# Main_Sheet.net
KiCad netlist of a schematic drawn in Altium Designer
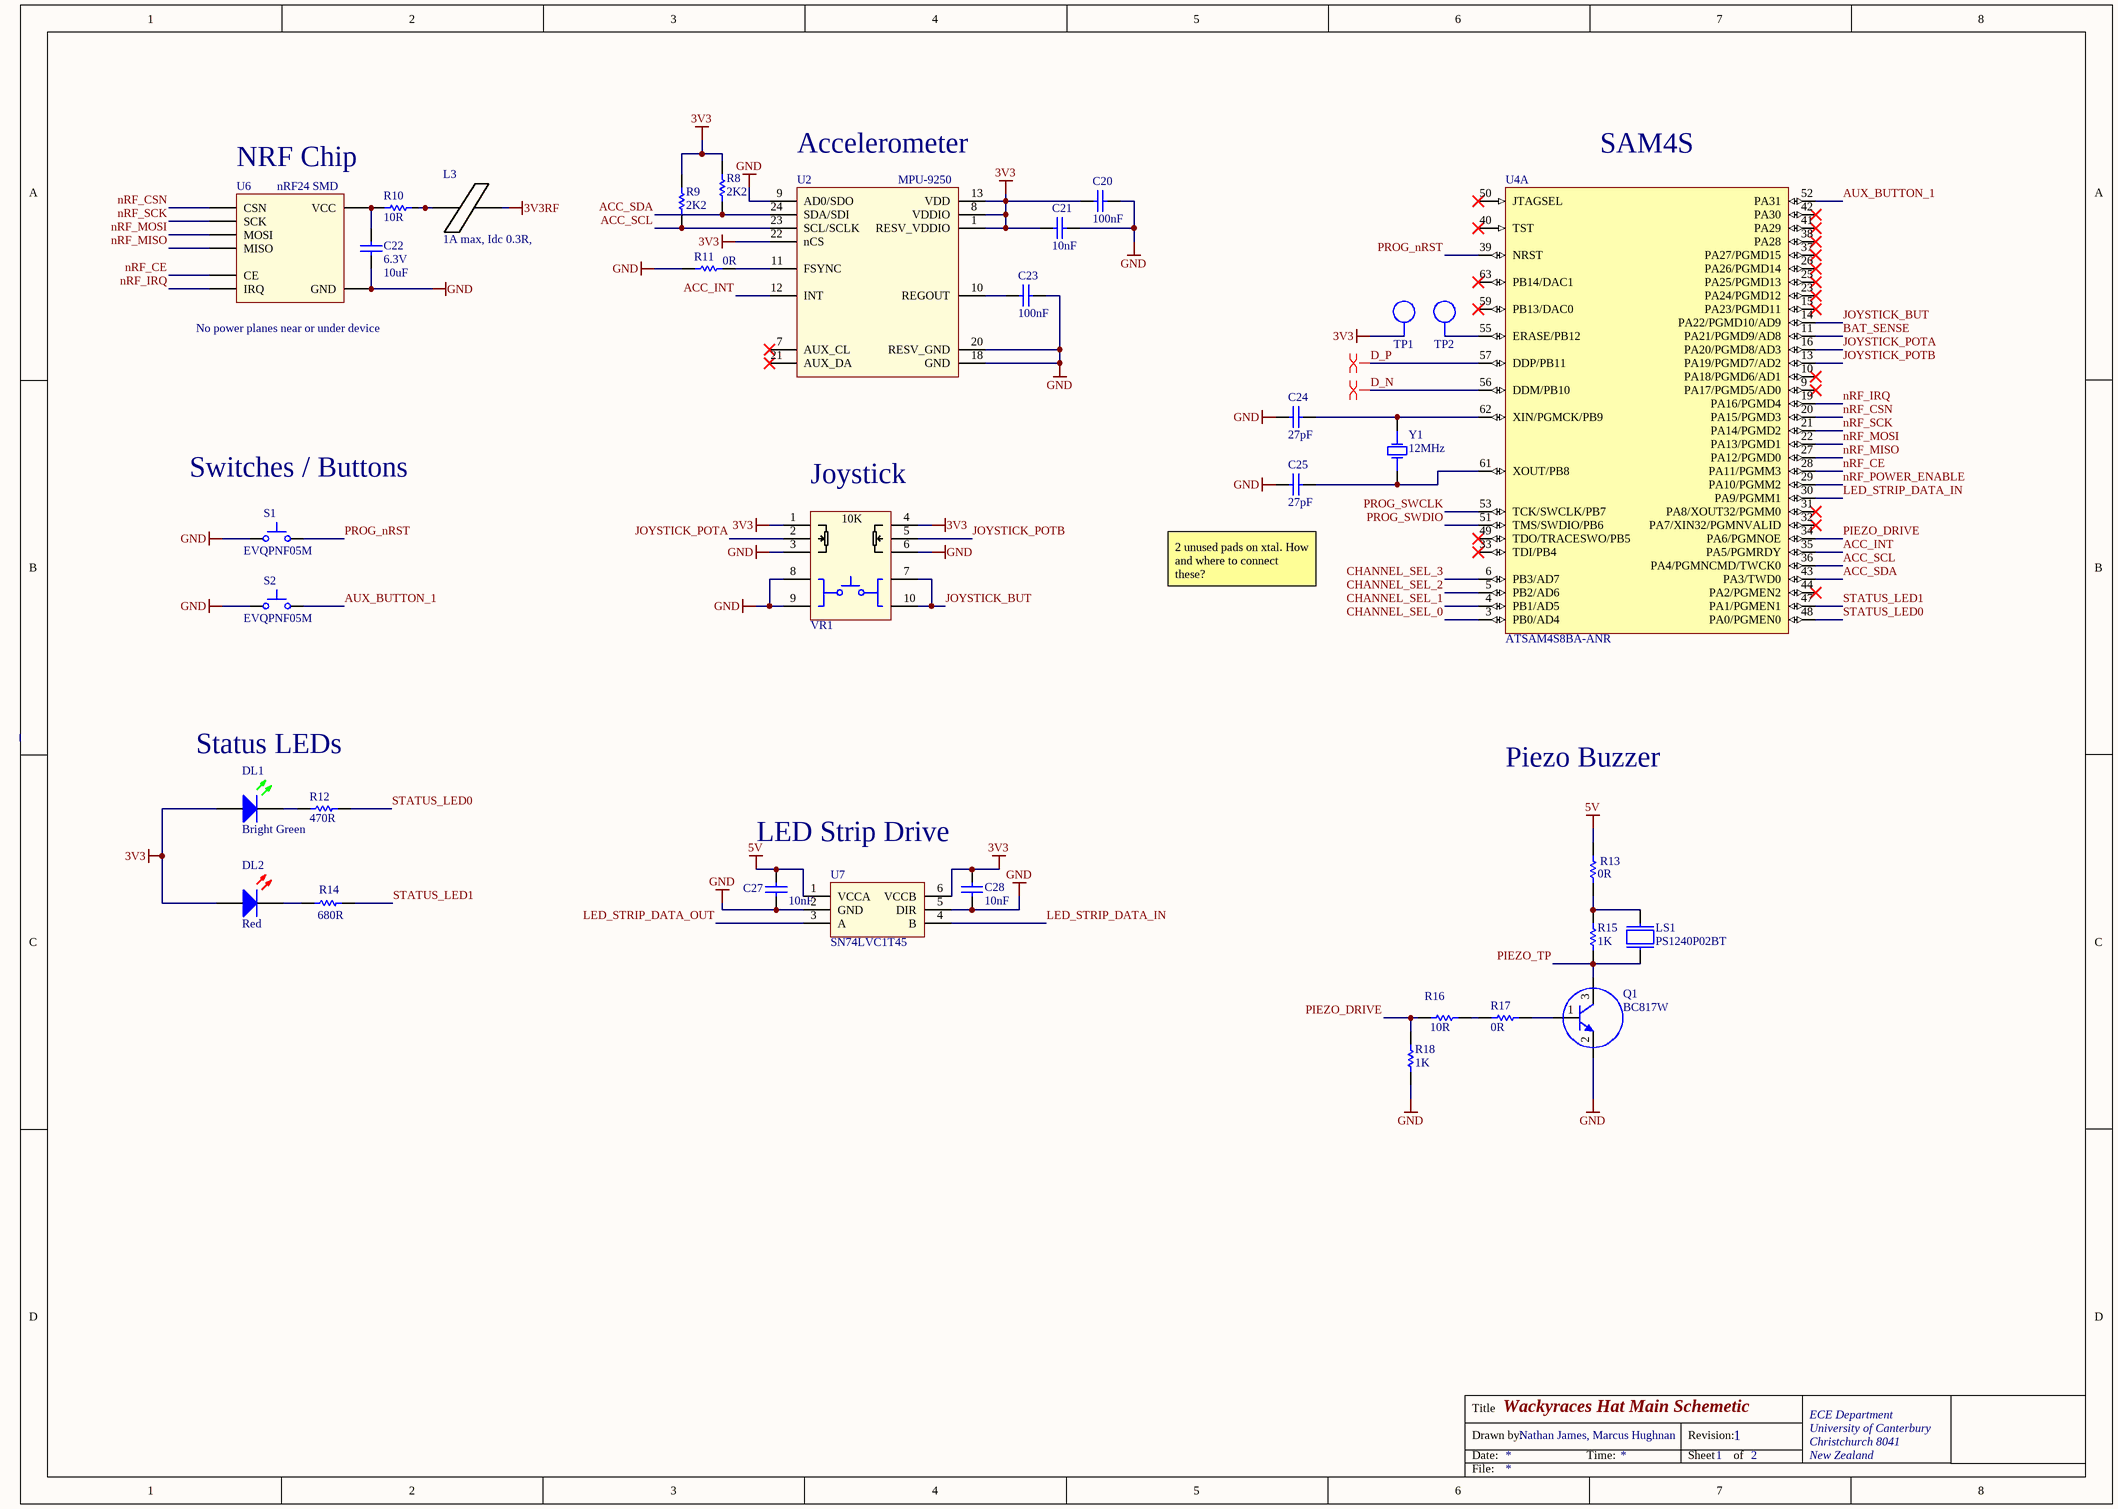
[diagram p0: Main Sheet.SchDoc]

(export (version "E")
  (design (tool "Eeschema 10.0.6"))
  (components
    (comp (ref "C20")
      (value "100nF")
      (footprint "CAPC1608L")
      (description "CAP CER 100nF X7R +-10% 50V 0603")
      (libsource (lib "ECE AD19Components_19V1") (part "CC_100nF_0603"))
    )
    (comp (ref "C21")
      (value "10nF")
      (footprint "CAPC1608L")
      (description "CAP CER 10nF X7R +-10% 50V 0603")
      (libsource (lib "ECE AD19Components_19V1") (part "CC_10nF_0603"))
    )
    (comp (ref "C22")
      (value "10uF")
      (footprint "CAPC1608L")
      (description "CAP CER 10UF X5R +-20% 6V3 0603")
      (fields (field (name "VOLTAGE - RATED") "6.3V"))
      (libsource (lib "ECE AD19Components_19V1") (part "CC_10uF_0603"))
    )
    (comp (ref "C23")
      (value "100nF")
      (footprint "CAPC1608L")
      (description "CAP CER 100nF X7R +-10% 50V 0603")
      (libsource (lib "ECE AD19Components_19V1") (part "CC_100nF_0603"))
    )
    (comp (ref "C24")
      (value "27pF")
      (footprint "CAPC1608L")
      (description "CAP CER 27pF NPO/COG +-5% 50V 0603")
      (libsource (lib "ECE AD19Components_19V1") (part "CC_27pF_0603"))
    )
    (comp (ref "C25")
      (value "27pF")
      (footprint "CAPC1608L")
      (description "CAP CER 27pF NPO/COG +-5% 50V 0603")
      (libsource (lib "ECE AD19Components_19V1") (part "CC_27pF_0603"))
    )
    (comp (ref "C27")
      (value "10nF")
      (footprint "CAPC1608L")
      (description "CAP CER 10nF X7R +-10% 50V 0603")
      (libsource (lib "ECE AD19Components_19V1") (part "CC_10nF_0603"))
    )
    (comp (ref "C28")
      (value "10nF")
      (footprint "CAPC1608L")
      (description "CAP CER 10nF X7R +-10% 50V 0603")
      (libsource (lib "ECE AD19Components_19V1") (part "CC_10nF_0603"))
    )
    (comp (ref "DL1")
      (value "Bright Green")
      (footprint "WL-SMCW0603")
      (description "LED Bright Green 40mcd 0603 SMD")
      (fields
        (field (name "MANUFACTURER") "WURTH ELEKTRONIK")
        (field (name "MANUFACTURER PART NUMBER") "150060VS75000")
        (field (name "LED COLOUR") "Bright Green")
      )
      (libsource (lib "ECE AD19Components_19V1") (part "DL_150060VS75000"))
    )
    (comp (ref "DL2")
      (value "Red")
      (footprint "WL-SMCW0603")
      (description "LED Red 250mcd 0603 SMD")
      (fields
        (field (name "MANUFACTURER") "WURTH ELEKTRONIK")
        (field (name "MANUFACTURER PART NUMBER") "150060RS75000")
        (field (name "LED COLOUR") "Red")
      )
      (libsource (lib "ECE AD19Components_19V1") (part "DL_150060RS75000"))
    )
    (comp (ref "L3")
      (value "1A max, Idc 0.3R,")
      (footprint "INDC3216L")
      (description "Ferrite Bead, Rdc 0.3R, Z100MHZ 600R, Imax 1A, SMD 1206")
      (fields
        (field (name "MANUFACTURER") "FAIR-RITE")
        (field (name "MANUFACTURER PART NUMBER") "2512066017Y1")
      )
      (libsource (lib "ECE AD19Components_19V1") (part "IN_Ferrite-Bead"))
    )
    (comp (ref "LS1")
      (value "PS1240P02BT")
      (footprint "XDCR_PS1240P02BT")
      (description "Buzzers Transducer, Externally Driven Piezo 3V 4kHz 60dB @ 3V, 10cm Through Hole PC Pins")
      (fields (field (name "MF") "TDK"))
      (libsource (lib "PS1240P02BT") (part "PS1240P02BT"))
    )
    (comp (ref "Q1")
      (value "BC817W")
      (footprint "SOT323_M")
      (description "NPN GP Bipolar Transistor 45V 500mA SOT323")
      (fields (field (name "MANUFACTURER") "NXP"))
      (libsource (lib "ECE AD19Components_19V1") (part "TB_BC817W"))
    )
    (comp (ref "R8")
      (value "2K2")
      (footprint "RESC1608L")
      (description "RES 2.2K OHM 1/10W 5% 0603 SMD")
      (libsource (lib "ECE AD19Components_19V1") (part "RS_2K2"))
    )
    (comp (ref "R9")
      (value "2K2")
      (footprint "RESC1608L")
      (description "RES 2.2K OHM 1/10W 5% 0603 SMD")
      (libsource (lib "ECE AD19Components_19V1") (part "RS_2K2"))
    )
    (comp (ref "R10")
      (value "10R")
      (footprint "RESC1608L")
      (description "RES 10 OHM 1/10W 5% 0603 SMD")
      (libsource (lib "ECE AD19Components_19V1") (part "RS_10R"))
    )
    (comp (ref "R11")
      (value "0R")
      (footprint "RESC1608L")
      (description "RES 0.0 OHM 1/10W 5% 0603 SMD")
      (libsource (lib "ECE AD19Components_19V1") (part "RS_0R0"))
    )
    (comp (ref "R12")
      (value "470R")
      (footprint "RESC1608L")
      (description "RES 470 OHM 1/10W 5% 0603 SMD")
      (libsource (lib "ECE AD19Components_19V1") (part "RS_470R"))
    )
    (comp (ref "R13")
      (value "0R")
      (footprint "RESC1608L")
      (description "RES 0.0 OHM 1/10W 5% 0603 SMD")
      (libsource (lib "ECE AD19Components_19V1") (part "RS_0R0"))
    )
    (comp (ref "R14")
      (value "680R")
      (footprint "RESC1608L")
      (description "RES 680 OHM 1/10W 5% 0603 SMD")
      (libsource (lib "ECE AD19Components_19V1") (part "RS_680R"))
    )
    (comp (ref "R15")
      (value "1K")
      (footprint "RESC1608L")
      (description "RES 1.0K OHM 1/10W 5% 0603 SMD")
      (libsource (lib "ECE AD19Components_19V1") (part "RS_1K"))
    )
    (comp (ref "R16")
      (value "10R")
      (footprint "RESC1608L")
      (description "RES 10 OHM 1/10W 5% 0603 SMD")
      (libsource (lib "ECE AD19Components_19V1") (part "RS_10R"))
    )
    (comp (ref "R17")
      (value "0R")
      (footprint "RESC1608L")
      (description "RES 0.0 OHM 1/10W 5% 0603 SMD")
      (libsource (lib "ECE AD19Components_19V1") (part "RS_0R0"))
    )
    (comp (ref "R18")
      (value "1K")
      (footprint "RESC1608L")
      (description "RES 1.0K OHM 1/10W 5% 0603 SMD")
      (libsource (lib "ECE AD19Components_19V1") (part "RS_1K"))
    )
    (comp (ref "S1")
      (value "EVQPNF05M")
      (footprint "EVQPNF05M")
      (description "Panasonic 6 x 3.5mm SMD Light Touch Switch Type SMD")
      (fields (field (name "MANUFACTURER") "Panasonic"))
      (libsource (lib "ECE AD19Components_19V1") (part "WS_EVQPNF05M"))
    )
    (comp (ref "S2")
      (value "EVQPNF05M")
      (footprint "EVQPNF05M")
      (description "Panasonic 6 x 3.5mm SMD Light Touch Switch Type SMD")
      (fields (field (name "MANUFACTURER") "Panasonic"))
      (libsource (lib "ECE AD19Components_19V1") (part "WS_EVQPNF05M"))
    )
    (comp (ref "TP1")
      (value "Erase")
      (footprint "TP_1206")
      (description "Test-Point 3.3x1.6x2.1mm SMD")
      (fields
        (field (name "MANUFACTURER") "Harwin Inc")
        (field (name "MANUFACTURER PART NUMBER") "S1751-46R")
      )
      (libsource (lib "ECE AD19Components_19V1") (part "TP_1206"))
    )
    (comp (ref "TP2")
      (value "Erase")
      (footprint "TP_1206")
      (description "Test-Point 3.3x1.6x2.1mm SMD")
      (fields
        (field (name "MANUFACTURER") "Harwin Inc")
        (field (name "MANUFACTURER PART NUMBER") "S1751-46R")
      )
      (libsource (lib "ECE AD19Components_19V1") (part "TP_1206"))
    )
    (comp (ref "U2")
      (value "MPU-9250")
      (footprint "Quad24")
      (description "9 axis IMU")
      (libsource (lib "ENCE461AD19_19V2") (part "MPU-9250"))
    )
    (comp (ref "U4")
      (value "ATSAM4S8BA-ANR")
      (footprint "LQFP64_L")
      (description "IC MCU 32BIT 512KB FLASH 64LQFP")
      (fields (field (name "MANUFACTURER") "Atmel"))
      (libsource (lib "ECE AD19Components_19V1") (part "SE_ATSAM4S16BA-MU"))
    )
    (comp (ref "U6")
      (value "nRF24 SMD")
      (footprint "NRF24")
      (description "nRF24 SMD Module")
      (fields (field (name "WARNING") "No power planes near or under device"))
      (libsource (lib "ENCE461AD19_19V2") (part "NRF24"))
    )
    (comp (ref "U7")
      (value "SN74LVC1T45")
      (footprint "SOT23-6_N")
      (description "1.8V - 5V level converter")
      (libsource (lib "ENCE461_extras_2020") (part "SN74LVC1T45"))
    )
    (comp (ref "VR1")
      (value "Joystick 10k with Sw")
      (footprint "Joystick_Sw")
      (description "JOYSTICK 10K OHM 2 AXIS TH")
      (libsource (lib "ENCE461AD19_19V2") (part "Joystick 10k with Sw"))
    )
    (comp (ref "Y1")
      (value "12MHz")
      (footprint "6.0X3.5-4")
      (description "CRYSTAL 12MHZ 18PF 6X3.5mm SMD")
      (fields
        (field (name "MANUFACTURER") "CTS-Frequency Controls")
        (field (name "MANUFACTURER PART NUMBER") "406C35D12M00000")
        (field (name "FREQUENCY") "12MHz")
      )
      (libsource (lib "ECE AD19Components_19V1") (part "XT_CRYSTAL_12MHz_18pF"))
    )
  )
  (nets
    (net (code "1") (name "/ACC_INT") (class "Default")
      (node (ref "U2") (pin "12") (pinfunction "INT_12") (pintype "passive"))
      (node (ref "U4") (pin "35") (pinfunction "PA5/PGMRDY_35") (pintype "bidirectional"))
    )
    (net (code "2") (name "/ACC_SCL") (class "Default")
      (node (ref "R9") (pin "2") (pinfunction "2_2") (pintype "passive"))
      (node (ref "U2") (pin "23") (pinfunction "SCL/SCLK_23") (pintype "passive"))
      (node (ref "U4") (pin "36") (pinfunction "PA4/PGMNCMD/TWCK0_36") (pintype "bidirectional"))
    )
    (net (code "3") (name "/ACC_SDA") (class "Default")
      (node (ref "R8") (pin "1") (pinfunction "1_1") (pintype "passive"))
      (node (ref "U2") (pin "24") (pinfunction "SDA/SDI_24") (pintype "passive"))
      (node (ref "U4") (pin "43") (pinfunction "PA3/TWD0_43") (pintype "bidirectional"))
    )
    (net (code "4") (name "/AUX_BUTTON_1") (class "Default")
      (node (ref "S2") (pin "2") (pintype "passive"))
      (node (ref "U4") (pin "52") (pinfunction "PA31_52") (pintype "bidirectional"))
    )
    (net (code "5") (name "/BAT_SENSE") (class "Default")
      (node (ref "U4") (pin "11") (pinfunction "PA21/PGMD9/AD8_11") (pintype "bidirectional"))
    )
    (net (code "6") (name "/CHANNEL_SEL_0") (class "Default")
      (node (ref "U4") (pin "3") (pinfunction "PB0/AD4_3") (pintype "bidirectional"))
    )
    (net (code "7") (name "/CHANNEL_SEL_1") (class "Default")
      (node (ref "U4") (pin "4") (pinfunction "PB1/AD5_4") (pintype "bidirectional"))
    )
    (net (code "8") (name "/CHANNEL_SEL_2") (class "Default")
      (node (ref "U4") (pin "5") (pinfunction "PB2/AD6_5") (pintype "bidirectional"))
    )
    (net (code "9") (name "/CHANNEL_SEL_3") (class "Default")
      (node (ref "U4") (pin "6") (pinfunction "PB3/AD7_6") (pintype "bidirectional"))
    )
    (net (code "10") (name "/D_N") (class "Default")
      (node (ref "U4") (pin "56") (pinfunction "DDM/PB10_56") (pintype "bidirectional"))
    )
    (net (code "11") (name "/D_P") (class "Default")
      (node (ref "U4") (pin "57") (pinfunction "DDP/PB11_57") (pintype "bidirectional"))
    )
    (net (code "12") (name "/JOYSTICK_BUT") (class "Default")
      (node (ref "U4") (pin "14") (pinfunction "PA22/PGMD10/AD9_14") (pintype "bidirectional"))
      (node (ref "VR1") (pin "10") (pinfunction "10_10") (pintype "passive"))
      (node (ref "VR1") (pin "7") (pinfunction "7_7") (pintype "passive"))
    )
    (net (code "13") (name "/JOYSTICK_POTA") (class "Default")
      (node (ref "U4") (pin "16") (pinfunction "PA20/PGMD8/AD3_16") (pintype "bidirectional"))
      (node (ref "VR1") (pin "2") (pinfunction "2_2") (pintype "passive"))
    )
    (net (code "14") (name "/JOYSTICK_POTB") (class "Default")
      (node (ref "U4") (pin "13") (pinfunction "PA19/PGMD7/AD2_13") (pintype "bidirectional"))
      (node (ref "VR1") (pin "5") (pinfunction "2'_5") (pintype "passive"))
    )
    (net (code "15") (name "/LED_STRIP_DATA_IN") (class "Default")
      (node (ref "U4") (pin "30") (pinfunction "PA9/PGMM1_30") (pintype "bidirectional"))
      (node (ref "U7") (pin "4") (pinfunction "B_4") (pintype "passive"))
    )
    (net (code "16") (name "/LED_STRIP_DATA_OUT") (class "Default")
      (node (ref "U7") (pin "3") (pinfunction "A_3") (pintype "passive"))
    )
    (net (code "17") (name "/PIEZO_DRIVE") (class "Default")
      (node (ref "R16") (pin "1") (pinfunction "1_1") (pintype "passive"))
      (node (ref "R18") (pin "2") (pinfunction "2_2") (pintype "passive"))
      (node (ref "U4") (pin "34") (pinfunction "PA6/PGMNOE_34") (pintype "bidirectional"))
    )
    (net (code "18") (name "/PIEZO_TP") (class "Default")
      (node (ref "LS1") (pin "1") (pinfunction "1_1") (pintype "passive"))
      (node (ref "Q1") (pin "3") (pinfunction "3_3") (pintype "passive"))
      (node (ref "R15") (pin "1") (pinfunction "1_1") (pintype "passive"))
    )
    (net (code "19") (name "/PROG_SWCLK") (class "Default")
      (node (ref "U4") (pin "53") (pinfunction "TCK/SWCLK/PB7_53") (pintype "bidirectional"))
    )
    (net (code "20") (name "/PROG_SWDIO") (class "Default")
      (node (ref "U4") (pin "51") (pinfunction "TMS/SWDIO/PB6_51") (pintype "bidirectional"))
    )
    (net (code "21") (name "/PROG_nRST") (class "Default")
      (node (ref "S1") (pin "2") (pintype "passive"))
      (node (ref "U4") (pin "39") (pinfunction "NRST_39") (pintype "bidirectional"))
    )
    (net (code "22") (name "/STATUS_LED0") (class "Default")
      (node (ref "R12") (pin "2") (pinfunction "2_2") (pintype "passive"))
      (node (ref "U4") (pin "48") (pinfunction "PA0/PGMEN0_48") (pintype "bidirectional"))
    )
    (net (code "23") (name "/STATUS_LED1") (class "Default")
      (node (ref "R14") (pin "2") (pinfunction "2_2") (pintype "passive"))
      (node (ref "U4") (pin "47") (pinfunction "PA1/PGMEN1_47") (pintype "bidirectional"))
    )
    (net (code "24") (name "/nRF_CE") (class "Default")
      (node (ref "U4") (pin "28") (pinfunction "PA11/PGMM3_28") (pintype "bidirectional"))
      (node (ref "U6") (pin "3") (pinfunction "CE_3") (pintype "passive"))
    )
    (net (code "25") (name "/nRF_CSN") (class "Default")
      (node (ref "U4") (pin "20") (pinfunction "PA15/PGMD3_20") (pintype "bidirectional"))
      (node (ref "U6") (pin "4") (pinfunction "CSN_4") (pintype "passive"))
    )
    (net (code "26") (name "/nRF_IRQ") (class "Default")
      (node (ref "U4") (pin "19") (pinfunction "PA16/PGMD4_19") (pintype "bidirectional"))
      (node (ref "U6") (pin "8") (pinfunction "IRQ_8") (pintype "passive"))
    )
    (net (code "27") (name "/nRF_MISO") (class "Default")
      (node (ref "U4") (pin "27") (pinfunction "PA12/PGMD0_27") (pintype "bidirectional"))
      (node (ref "U6") (pin "7") (pinfunction "MISO_7") (pintype "passive"))
    )
    (net (code "28") (name "/nRF_MOSI") (class "Default")
      (node (ref "U4") (pin "22") (pinfunction "PA13/PGMD1_22") (pintype "bidirectional"))
      (node (ref "U6") (pin "6") (pinfunction "MOSI_6") (pintype "passive"))
    )
    (net (code "29") (name "/nRF_POWER_ENABLE") (class "Default")
      (node (ref "U4") (pin "29") (pinfunction "PA10/PGMM2_29") (pintype "bidirectional"))
    )
    (net (code "30") (name "/nRF_SCK") (class "Default")
      (node (ref "U4") (pin "21") (pinfunction "PA14/PGMD2_21") (pintype "bidirectional"))
      (node (ref "U6") (pin "5") (pinfunction "SCK_5") (pintype "passive"))
    )
    (net (code "31") (name "3V3") (class "Default")
      (node (ref "C20") (pin "1") (pinfunction "1_1") (pintype "passive"))
      (node (ref "C21") (pin "1") (pinfunction "1_1") (pintype "passive"))
      (node (ref "C28") (pin "2") (pinfunction "2_2") (pintype "passive"))
      (node (ref "DL1") (pin "2") (pinfunction "A_2") (pintype "passive"))
      (node (ref "DL2") (pin "2") (pinfunction "A_2") (pintype "passive"))
      (node (ref "R8") (pin "2") (pinfunction "2_2") (pintype "passive"))
      (node (ref "R9") (pin "1") (pinfunction "1_1") (pintype "passive"))
      (node (ref "TP1") (pin "1") (pinfunction "1_1") (pintype "passive"))
      (node (ref "U2") (pin "1") (pinfunction "RESV_VDDIO_1") (pintype "passive"))
      (node (ref "U2") (pin "13") (pinfunction "VDD_13") (pintype "passive"))
      (node (ref "U2") (pin "22") (pinfunction "nCS_22") (pintype "passive"))
      (node (ref "U2") (pin "8") (pinfunction "VDDIO_8") (pintype "passive"))
      (node (ref "U7") (pin "6") (pinfunction "VCCB_6") (pintype "passive"))
      (node (ref "VR1") (pin "1") (pinfunction "1_1") (pintype "passive"))
      (node (ref "VR1") (pin "4") (pinfunction "1'_4") (pintype "passive"))
    )
    (net (code "32") (name "3V3RF") (class "Default")
      (node (ref "L3") (pin "1") (pinfunction "1_1") (pintype "passive"))
    )
    (net (code "33") (name "5V") (class "Default")
      (node (ref "C27") (pin "2") (pinfunction "2_2") (pintype "passive"))
      (node (ref "R13") (pin "2") (pinfunction "2_2") (pintype "passive"))
      (node (ref "U7") (pin "1") (pinfunction "VCCA_1") (pintype "passive"))
    )
    (net (code "34") (name "GND") (class "Default")
      (node (ref "C20") (pin "2") (pinfunction "2_2") (pintype "passive"))
      (node (ref "C21") (pin "2") (pinfunction "2_2") (pintype "passive"))
      (node (ref "C22") (pin "1") (pinfunction "1_1") (pintype "passive"))
      (node (ref "C23") (pin "2") (pinfunction "2_2") (pintype "passive"))
      (node (ref "C24") (pin "1") (pinfunction "1_1") (pintype "passive"))
      (node (ref "C25") (pin "1") (pinfunction "1_1") (pintype "passive"))
      (node (ref "C27") (pin "1") (pinfunction "1_1") (pintype "passive"))
      (node (ref "C28") (pin "1") (pinfunction "1_1") (pintype "passive"))
      (node (ref "Q1") (pin "2") (pinfunction "2_2") (pintype "passive"))
      (node (ref "R11") (pin "1") (pinfunction "1_1") (pintype "passive"))
      (node (ref "R18") (pin "1") (pinfunction "1_1") (pintype "passive"))
      (node (ref "S1") (pin "1") (pintype "passive"))
      (node (ref "S2") (pin "1") (pintype "passive"))
      (node (ref "U2") (pin "18") (pinfunction "GND_18") (pintype "passive"))
      (node (ref "U2") (pin "20") (pinfunction "RESV_GND_20") (pintype "passive"))
      (node (ref "U2") (pin "9") (pinfunction "AD0/SDO_9") (pintype "passive"))
      (node (ref "U6") (pin "2") (pinfunction "GND_2") (pintype "passive"))
      (node (ref "U7") (pin "2") (pinfunction "GND_2") (pintype "passive"))
      (node (ref "U7") (pin "5") (pinfunction "DIR_5") (pintype "passive"))
      (node (ref "VR1") (pin "3") (pinfunction "3_3") (pintype "passive"))
      (node (ref "VR1") (pin "6") (pinfunction "3'_6") (pintype "passive"))
      (node (ref "VR1") (pin "8") (pinfunction "8_8") (pintype "passive"))
      (node (ref "VR1") (pin "9") (pinfunction "9_9") (pintype "passive"))
    )
    (net (code "35") (name "Net-(DL1-K)") (class "Default")
      (node (ref "DL1") (pin "1") (pinfunction "K_1") (pintype "passive"))
      (node (ref "R12") (pin "1") (pinfunction "1_1") (pintype "passive"))
    )
    (net (code "36") (name "Net-(DL2-K)") (class "Default")
      (node (ref "DL2") (pin "1") (pinfunction "K_1") (pintype "passive"))
      (node (ref "R14") (pin "1") (pinfunction "1_1") (pintype "passive"))
    )
    (net (code "37") (name "Net-(L3-Pad2)") (class "Default")
      (node (ref "L3") (pin "2") (pinfunction "2_2") (pintype "passive"))
      (node (ref "R10") (pin "2") (pinfunction "2_2") (pintype "passive"))
    )
    (net (code "38") (name "Net-(LS1-Pad2)") (class "Default")
      (node (ref "LS1") (pin "2") (pinfunction "2_2") (pintype "passive"))
      (node (ref "R13") (pin "1") (pinfunction "1_1") (pintype "passive"))
      (node (ref "R15") (pin "2") (pinfunction "2_2") (pintype "passive"))
    )
    (net (code "39") (name "Net-(Q1-Pad1)") (class "Default")
      (node (ref "Q1") (pin "1") (pinfunction "1_1") (pintype "passive"))
      (node (ref "R17") (pin "2") (pinfunction "2_2") (pintype "passive"))
    )
    (net (code "40") (name "Net-(R16-Pad2)") (class "Default")
      (node (ref "R16") (pin "2") (pinfunction "2_2") (pintype "passive"))
      (node (ref "R17") (pin "1") (pinfunction "1_1") (pintype "passive"))
    )
    (net (code "41") (name "Net-(U2-FSYNC)") (class "Default")
      (node (ref "R11") (pin "2") (pinfunction "2_2") (pintype "passive"))
      (node (ref "U2") (pin "11") (pinfunction "FSYNC_11") (pintype "passive"))
    )
    (net (code "42") (name "Net-(U2-REGOUT)") (class "Default")
      (node (ref "C23") (pin "1") (pinfunction "1_1") (pintype "passive"))
      (node (ref "U2") (pin "10") (pinfunction "REGOUT_10") (pintype "passive"))
    )
    (net (code "43") (name "Net-(U4A-ERASE{slash}PB12)") (class "Default")
      (node (ref "TP2") (pin "1") (pinfunction "1_1") (pintype "passive"))
      (node (ref "U4") (pin "55") (pinfunction "ERASE/PB12_55") (pintype "bidirectional"))
    )
    (net (code "44") (name "Net-(U4A-XIN{slash}PGMCK{slash}PB9)") (class "Default")
      (node (ref "C24") (pin "2") (pinfunction "2_2") (pintype "passive"))
      (node (ref "U4") (pin "62") (pinfunction "XIN/PGMCK/PB9_62") (pintype "bidirectional"))
      (node (ref "Y1") (pin "3") (pinfunction "OSC2_3") (pintype "passive"))
    )
    (net (code "45") (name "Net-(U4A-XOUT{slash}PB8)") (class "Default")
      (node (ref "C25") (pin "2") (pinfunction "2_2") (pintype "passive"))
      (node (ref "U4") (pin "61") (pinfunction "XOUT/PB8_61") (pintype "bidirectional"))
      (node (ref "Y1") (pin "1") (pinfunction "OSC1_1") (pintype "passive"))
    )
    (net (code "46") (name "Net-(U6-VCC)") (class "Default")
      (node (ref "C22") (pin "2") (pinfunction "2_2") (pintype "passive"))
      (node (ref "R10") (pin "1") (pinfunction "1_1") (pintype "passive"))
      (node (ref "U6") (pin "1") (pinfunction "VCC_1") (pintype "passive"))
    )
    (net (code "47") (name "unconnected-(U2-AUX_CL-Pad7)") (class "Default")
      (node (ref "U2") (pin "7") (pinfunction "AUX_CL_7") (pintype "passive+no_connect"))
    )
    (net (code "48") (name "unconnected-(U2-AUX_DA-Pad21)") (class "Default")
      (node (ref "U2") (pin "21") (pinfunction "AUX_DA_21") (pintype "passive+no_connect"))
    )
    (net (code "49") (name "unconnected-(U4A-JTAGSEL-Pad50)") (class "Default")
      (node (ref "U4") (pin "50") (pinfunction "JTAGSEL_50") (pintype "input+no_connect"))
    )
    (net (code "50") (name "unconnected-(U4A-PA2{slash}PGMEN2-Pad44)") (class "Default")
      (node (ref "U4") (pin "44") (pinfunction "PA2/PGMEN2_44") (pintype "bidirectional+no_connect"))
    )
    (net (code "51") (name "unconnected-(U4A-PA7{slash}XIN32{slash}PGMNVALID-Pad32)") (class "Default")
      (node (ref "U4") (pin "32") (pinfunction "PA7/XIN32/PGMNVALID_32") (pintype "bidirectional+no_connect"))
    )
    (net (code "52") (name "unconnected-(U4A-PA8{slash}XOUT32{slash}PGMM0-Pad31)") (class "Default")
      (node (ref "U4") (pin "31") (pinfunction "PA8/XOUT32/PGMM0_31") (pintype "bidirectional+no_connect"))
    )
    (net (code "53") (name "unconnected-(U4A-PA17{slash}PGMD5{slash}AD0-Pad9)") (class "Default")
      (node (ref "U4") (pin "9") (pinfunction "PA17/PGMD5/AD0_9") (pintype "bidirectional+no_connect"))
    )
    (net (code "54") (name "unconnected-(U4A-PA18{slash}PGMD6{slash}AD1-Pad10)") (class "Default")
      (node (ref "U4") (pin "10") (pinfunction "PA18/PGMD6/AD1_10") (pintype "bidirectional+no_connect"))
    )
    (net (code "55") (name "unconnected-(U4A-PA23{slash}PGMD11-Pad15)") (class "Default")
      (node (ref "U4") (pin "15") (pinfunction "PA23/PGMD11_15") (pintype "bidirectional+no_connect"))
    )
    (net (code "56") (name "unconnected-(U4A-PA24{slash}PGMD12-Pad23)") (class "Default")
      (node (ref "U4") (pin "23") (pinfunction "PA24/PGMD12_23") (pintype "bidirectional+no_connect"))
    )
    (net (code "57") (name "unconnected-(U4A-PA25{slash}PGMD13-Pad25)") (class "Default")
      (node (ref "U4") (pin "25") (pinfunction "PA25/PGMD13_25") (pintype "bidirectional+no_connect"))
    )
    (net (code "58") (name "unconnected-(U4A-PA26{slash}PGMD14-Pad26)") (class "Default")
      (node (ref "U4") (pin "26") (pinfunction "PA26/PGMD14_26") (pintype "bidirectional+no_connect"))
    )
    (net (code "59") (name "unconnected-(U4A-PA27{slash}PGMD15-Pad37)") (class "Default")
      (node (ref "U4") (pin "37") (pinfunction "PA27/PGMD15_37") (pintype "bidirectional+no_connect"))
    )
    (net (code "60") (name "unconnected-(U4A-PA28-Pad38)") (class "Default")
      (node (ref "U4") (pin "38") (pinfunction "PA28_38") (pintype "bidirectional+no_connect"))
    )
    (net (code "61") (name "unconnected-(U4A-PA29-Pad41)") (class "Default")
      (node (ref "U4") (pin "41") (pinfunction "PA29_41") (pintype "bidirectional+no_connect"))
    )
    (net (code "62") (name "unconnected-(U4A-PA30-Pad42)") (class "Default")
      (node (ref "U4") (pin "42") (pinfunction "PA30_42") (pintype "bidirectional+no_connect"))
    )
    (net (code "63") (name "unconnected-(U4A-PB13{slash}DAC0-Pad59)") (class "Default")
      (node (ref "U4") (pin "59") (pinfunction "PB13/DAC0_59") (pintype "bidirectional+no_connect"))
    )
    (net (code "64") (name "unconnected-(U4A-PB14{slash}DAC1-Pad63)") (class "Default")
      (node (ref "U4") (pin "63") (pinfunction "PB14/DAC1_63") (pintype "bidirectional+no_connect"))
    )
    (net (code "65") (name "unconnected-(U4A-TDI{slash}PB4-Pad33)") (class "Default")
      (node (ref "U4") (pin "33") (pinfunction "TDI/PB4_33") (pintype "bidirectional+no_connect"))
    )
    (net (code "66") (name "unconnected-(U4A-TDO{slash}TRACESWO{slash}PB5-Pad49)") (class "Default")
      (node (ref "U4") (pin "49") (pinfunction "TDO/TRACESWO/PB5_49") (pintype "bidirectional+no_connect"))
    )
    (net (code "67") (name "unconnected-(U4A-TST-Pad40)") (class "Default")
      (node (ref "U4") (pin "40") (pinfunction "TST_40") (pintype "input+no_connect"))
    )
  )
)
